# eCog111_16ch_PWM_Servo.net
KiCad netlist of a schematic drawn in EAGLE
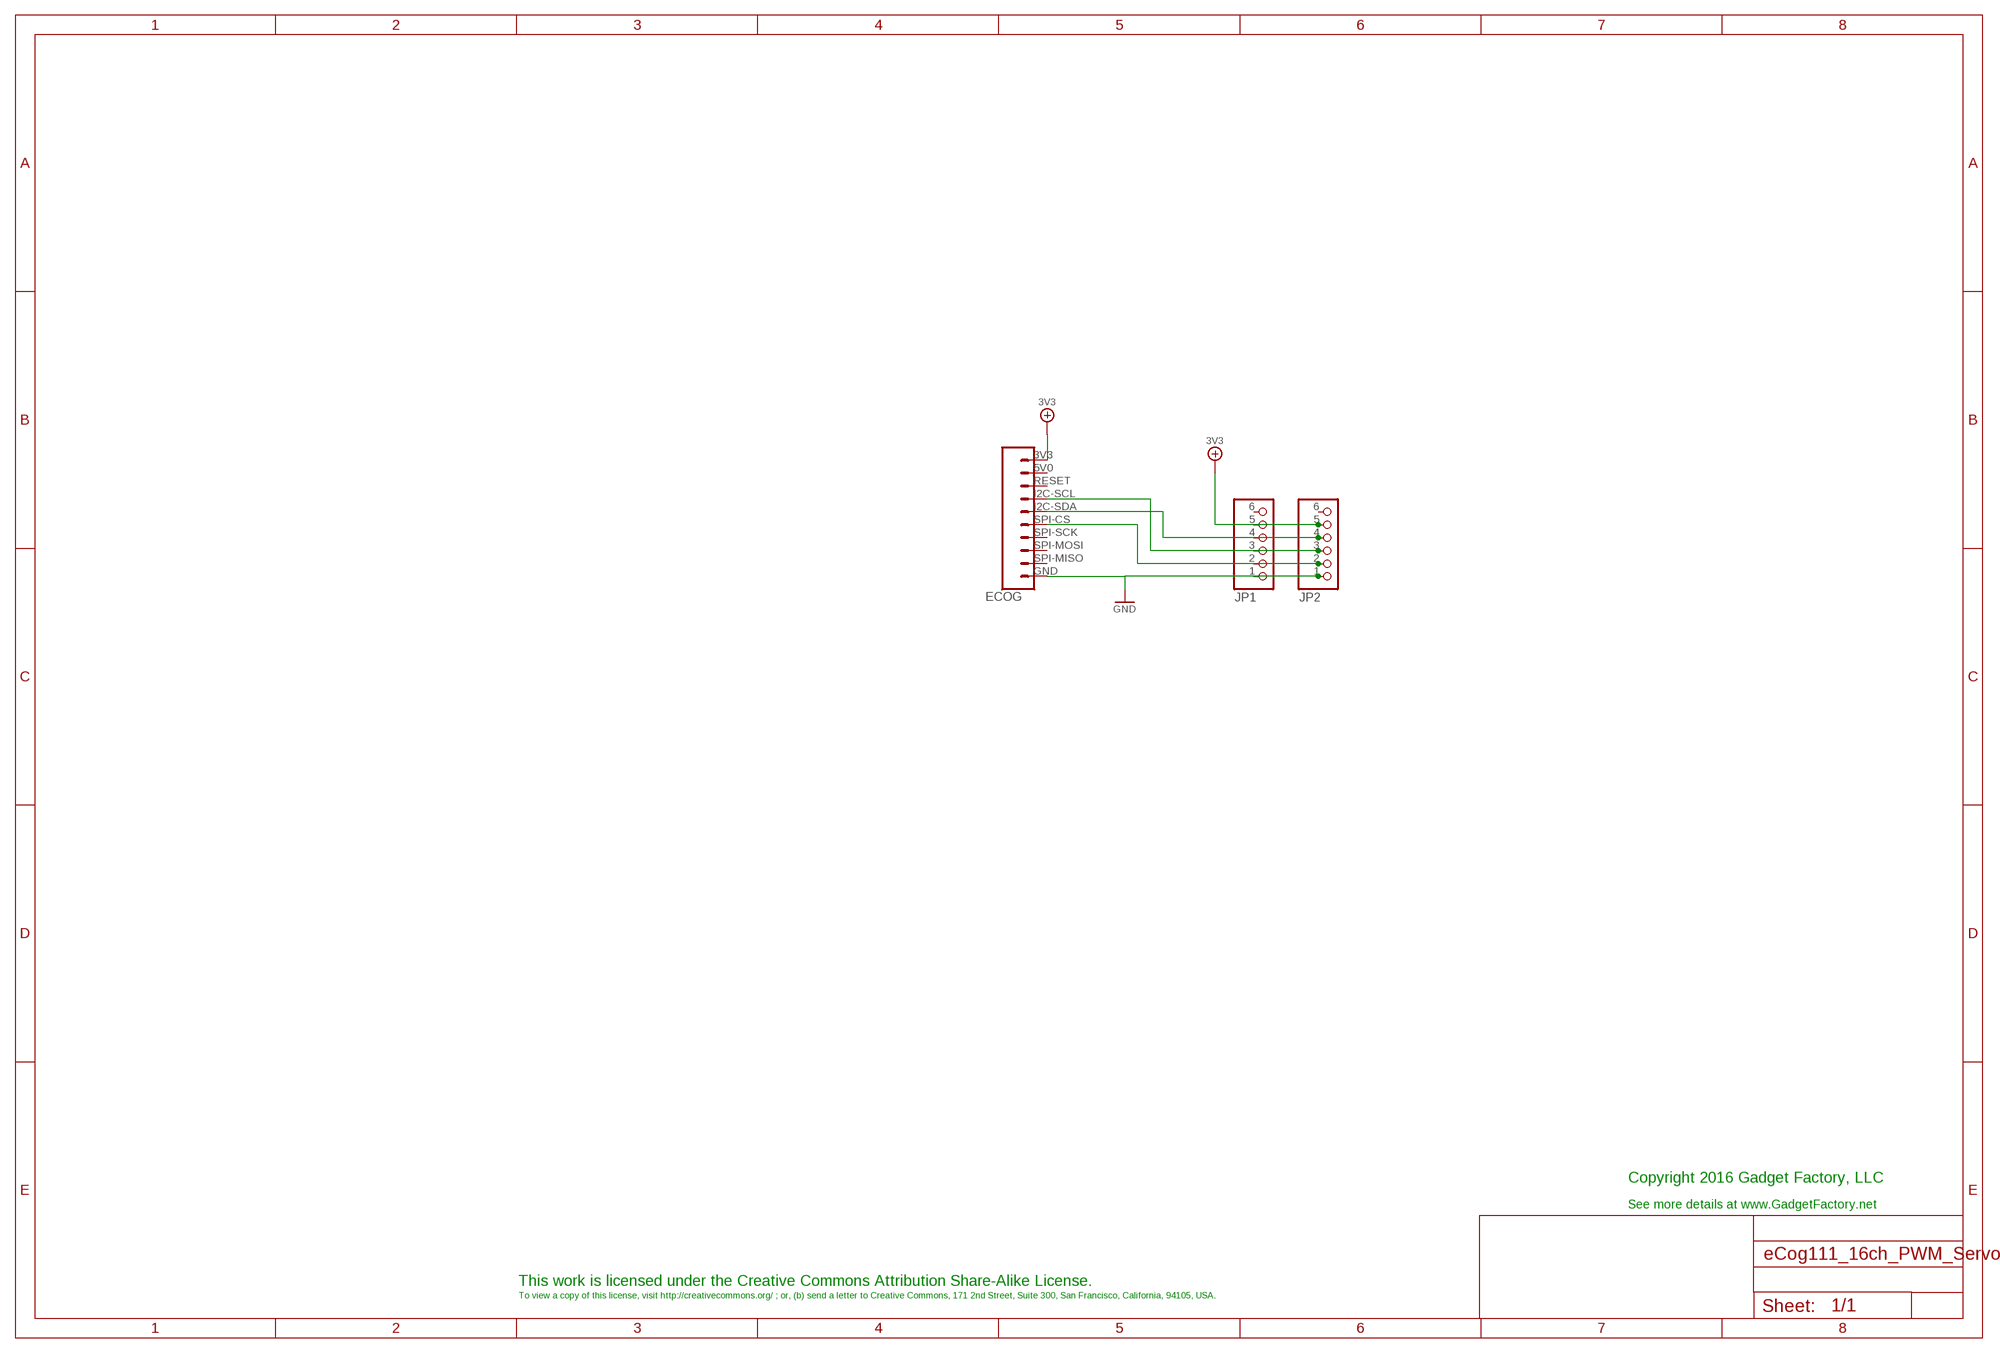
[diagram p0: schematic, sheet 1]

(export (version "E")
  (design (tool "Eeschema 10.0.6"))
  (components
    (comp (ref "ECOG")
      (value "ECOG_BUSES_ROWTHROUGHHOLE")
      (footprint "eagle-import:ECOG_BUSES_TH")
      (libsource (lib "eagle-import") (part "ECOG_BUSES_ROWTHROUGHHOLE"))
    )
    (comp (ref "JP1")
      (value "PINHD-1X6")
      (footprint "eagle-import:1X06")
      (libsource (lib "eagle-import") (part "PINHD-1X6"))
    )
    (comp (ref "JP2")
      (value "PINHD-1X6")
      (footprint "eagle-import:1X06")
      (libsource (lib "eagle-import") (part "PINHD-1X6"))
    )
  )
  (nets
    (net (code "1") (name "3V3") (class "Default")
      (node (ref "ECOG") (pin "3V3") (pinfunction "3V3_3V3") (pintype "passive"))
      (node (ref "JP1") (pin "5") (pinfunction "5_5") (pintype "passive"))
      (node (ref "JP2") (pin "5") (pinfunction "5_5") (pintype "passive"))
    )
    (net (code "2") (name "GND") (class "Default")
      (node (ref "ECOG") (pin "GND") (pinfunction "GND_GND") (pintype "passive"))
      (node (ref "JP1") (pin "1") (pinfunction "1_1") (pintype "passive"))
      (node (ref "JP2") (pin "1") (pinfunction "1_1") (pintype "passive"))
    )
    (net (code "3") (name "Net-(ECOG-PadI2C-SCL)") (class "Default")
      (node (ref "ECOG") (pin "I2C-SCL") (pinfunction "I2C-SCL_I2C-SCL") (pintype "passive"))
      (node (ref "JP1") (pin "3") (pinfunction "3_3") (pintype "passive"))
      (node (ref "JP2") (pin "3") (pinfunction "3_3") (pintype "passive"))
    )
    (net (code "4") (name "Net-(ECOG-PadI2C-SDA)") (class "Default")
      (node (ref "ECOG") (pin "I2C-SDA") (pinfunction "I2C-SDA_I2C-SDA") (pintype "passive"))
      (node (ref "JP1") (pin "4") (pinfunction "4_4") (pintype "passive"))
      (node (ref "JP2") (pin "4") (pinfunction "4_4") (pintype "passive"))
    )
    (net (code "5") (name "Net-(ECOG-PadSPI-CS)") (class "Default")
      (node (ref "ECOG") (pin "SPI-CS") (pinfunction "SPI-CS_SPI-CS") (pintype "passive"))
      (node (ref "JP1") (pin "2") (pinfunction "2_2") (pintype "passive"))
      (node (ref "JP2") (pin "2") (pinfunction "2_2") (pintype "passive"))
    )
    (net (code "6") (name "unconnected-(ECOG-PadSPI-MISO)") (class "Default")
      (node (ref "ECOG") (pin "SPI-MISO") (pinfunction "SPI-MISO_SPI-MISO") (pintype "passive"))
    )
    (net (code "7") (name "unconnected-(ECOG-PadSPI-MOSI)") (class "Default")
      (node (ref "ECOG") (pin "SPI-MOSI") (pinfunction "SPI-MOSI_SPI-MOSI") (pintype "passive"))
    )
    (net (code "8") (name "unconnected-(ECOG-PadSPI-SCK)") (class "Default")
      (node (ref "ECOG") (pin "SPI-SCK") (pinfunction "SPI-SCK_SPI-SCK") (pintype "passive"))
    )
    (net (code "9") (name "unconnected-(ECOG-RSV-Pad5V0)") (class "Default")
      (node (ref "ECOG") (pin "5V0") (pinfunction "RSV_5V0") (pintype "passive"))
    )
    (net (code "10") (name "unconnected-(ECOG-RSV-PadRESET)") (class "Default")
      (node (ref "ECOG") (pin "RESET") (pinfunction "RSV_RESET") (pintype "passive"))
    )
    (net (code "11") (name "unconnected-(JP1-Pad6)") (class "Default")
      (node (ref "JP1") (pin "6") (pinfunction "6_6") (pintype "passive"))
    )
    (net (code "12") (name "unconnected-(JP2-Pad6)") (class "Default")
      (node (ref "JP2") (pin "6") (pinfunction "6_6") (pintype "passive"))
    )
  )
)
